# SoftCore_SA_P6.net
KiCad netlist of a schematic drawn in Altium Designer
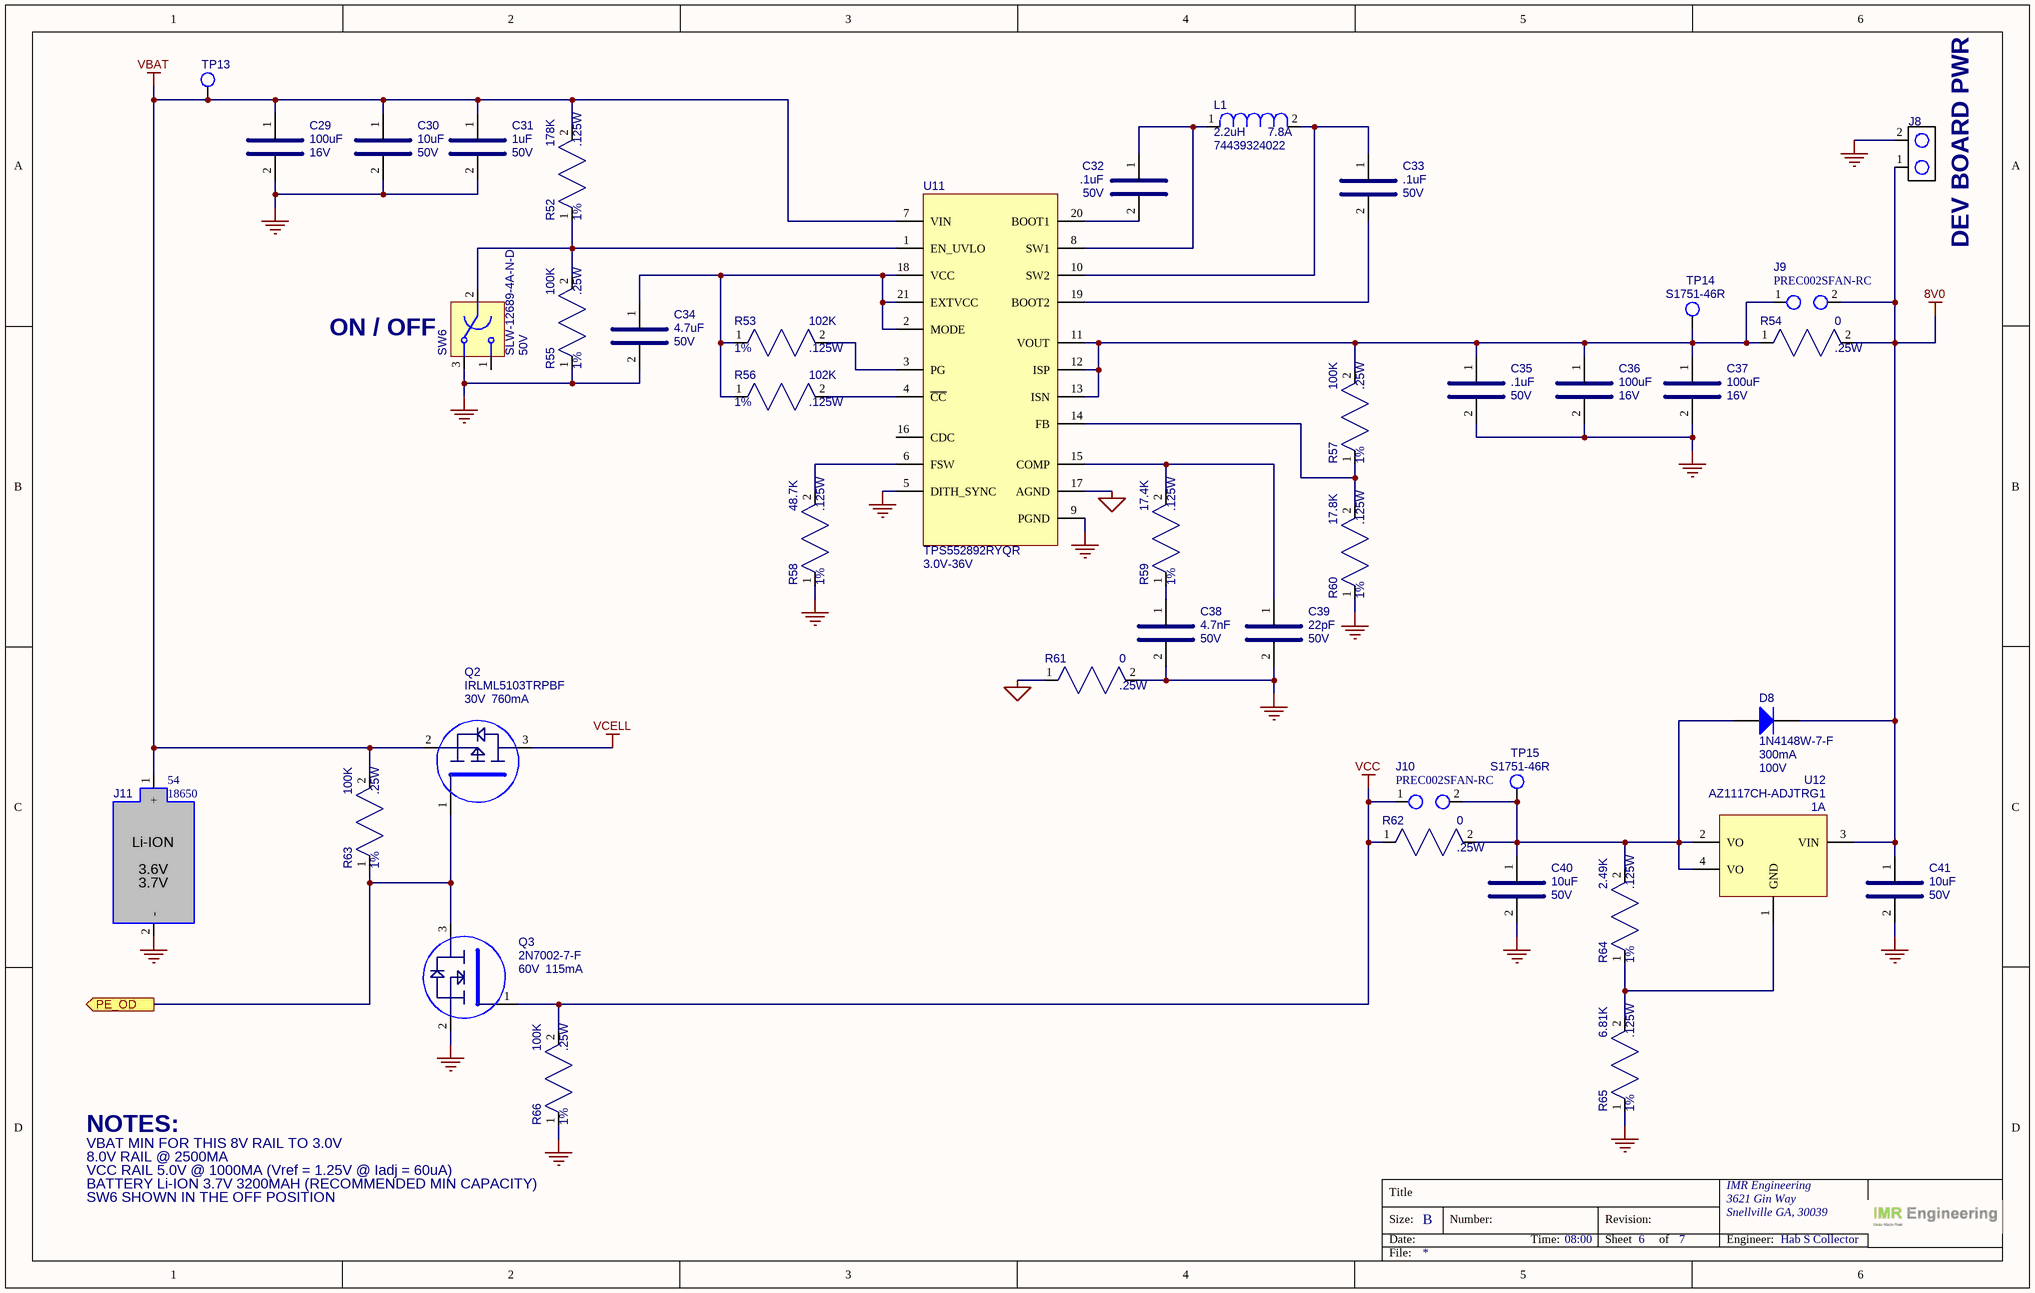
[diagram p0: SoftCore_SA_P6.SchDoc]

(export (version "E")
  (design (tool "Eeschema 10.0.6"))
  (components
    (comp (ref "C29")
      (value "100uF")
      (footprint "CAP_1210")
      (description "CAP CER 100UF 16V X7S SMD")
      (fields
        (field (name "MFG") "Taiyo Yuden")
        (field (name "VOLTAGE") "16V")
        (field (name "Comment") "EMK325ABJ107MM-P")
      )
      (libsource (lib "IMR_LIB_SCH_R2") (part "CAP_SMD_100UF_16V_SMD"))
    )
    (comp (ref "C30")
      (value "10uF")
      (footprint "CAP_0805")
      (description "CAP CER 10UF 50V X5R 0805")
      (fields
        (field (name "MFG") "Murata Electronics")
        (field (name "VOLTAGE") "50V")
        (field (name "Comment") "GRM21BR61H106KE43L")
      )
      (libsource (lib "IMR_LIB_SCH_R2") (part "CAP_SMD_10UF_50V_0805"))
    )
    (comp (ref "C31")
      (value "1uF")
      (footprint "CAP_0805")
      (description "CAP CER 1UF 50V X7R 0805")
      (fields
        (field (name "MFG") "KYOCERA AVX")
        (field (name "VOLTAGE") "50V")
        (field (name "Comment") "08055C105K4T2A")
      )
      (libsource (lib "IMR_LIB_SCH_R2") (part "CAP_SMD_1UF_50V_0805"))
    )
    (comp (ref "C32")
      (value ".1uF")
      (footprint "CAP_0805")
      (description "CAP CER 0.1UF 50V X7R 0805")
      (fields
        (field (name "MFG") "KYOCERA AVX")
        (field (name "VOLTAGE") "50V")
        (field (name "Comment") "KGM21NR71H104KT")
      )
      (libsource (lib "IMR_LIB_SCH_R2") (part "CAP_SMD_0.1UF_50V_0805"))
    )
    (comp (ref "C33")
      (value ".1uF")
      (footprint "CAP_0805")
      (description "CAP CER 0.1UF 50V X7R 0805")
      (fields
        (field (name "MFG") "KYOCERA AVX")
        (field (name "VOLTAGE") "50V")
        (field (name "Comment") "KGM21NR71H104KT")
      )
      (libsource (lib "IMR_LIB_SCH_R2") (part "CAP_SMD_0.1UF_50V_0805"))
    )
    (comp (ref "C34")
      (value "4.7uF")
      (footprint "CAP_0805")
      (description "CAP CER 4.7UF 50V X5R 0805")
      (fields
        (field (name "MFG") "Murata Electronics")
        (field (name "VOLTAGE") "50V")
        (field (name "Comment") "GRM21BR61H475KE51L")
      )
      (libsource (lib "IMR_LIB_SCH_R2") (part "CAP_SMD_4.7UF_50V_0805"))
    )
    (comp (ref "C35")
      (value ".1uF")
      (footprint "CAP_0805")
      (description "CAP CER 0.1UF 50V X7R 0805")
      (fields
        (field (name "MFG") "KYOCERA AVX")
        (field (name "VOLTAGE") "50V")
        (field (name "Comment") "KGM21NR71H104KT")
      )
      (libsource (lib "IMR_LIB_SCH_R2") (part "CAP_SMD_0.1UF_50V_0805"))
    )
    (comp (ref "C36")
      (value "100uF")
      (footprint "CAP_1210")
      (description "CAP CER 100UF 16V X7S SMD")
      (fields
        (field (name "MFG") "Taiyo Yuden")
        (field (name "VOLTAGE") "16V")
        (field (name "Comment") "EMK325ABJ107MM-P")
      )
      (libsource (lib "IMR_LIB_SCH_R2") (part "CAP_SMD_100UF_16V_SMD"))
    )
    (comp (ref "C37")
      (value "100uF")
      (footprint "CAP_1210")
      (description "CAP CER 100UF 16V X7S SMD")
      (fields
        (field (name "MFG") "Taiyo Yuden")
        (field (name "VOLTAGE") "16V")
        (field (name "Comment") "EMK325ABJ107MM-P")
      )
      (libsource (lib "IMR_LIB_SCH_R2") (part "CAP_SMD_100UF_16V_SMD"))
    )
    (comp (ref "C38")
      (value "4.7nF")
      (footprint "CAP_0805")
      (description "CAP CER 4.7NF 50V X7R 0805")
      (fields
        (field (name "MFG") "KEMET")
        (field (name "VOLTAGE") "50V")
        (field (name "Comment") "C0805C472K5RACAUTO")
      )
      (libsource (lib "IMR_LIB_SCH_R2") (part "CAP_SMD_4.7NF_50V_0805"))
    )
    (comp (ref "C39")
      (value "22pF")
      (footprint "CAP_0805")
      (description "CAP CER 22PF 50V X7R 0805")
      (fields
        (field (name "MFG") "KEMET")
        (field (name "VOLTAGE") "50V")
        (field (name "Comment") "C0805C220K5RACAUTO")
      )
      (libsource (lib "IMR_LIB_SCH_R2") (part "CAP_SMD_22PF_50V_0805"))
    )
    (comp (ref "C40")
      (value "10uF")
      (footprint "CAP_0805")
      (description "CAP CER 10UF 50V X5R 0805")
      (fields
        (field (name "MFG") "Murata Electronics")
        (field (name "VOLTAGE") "50V")
        (field (name "Comment") "GRM21BR61H106KE43L")
      )
      (libsource (lib "IMR_LIB_SCH_R2") (part "CAP_SMD_10UF_50V_0805"))
    )
    (comp (ref "C41")
      (value "10uF")
      (footprint "CAP_0805")
      (description "CAP CER 10UF 50V X5R 0805")
      (fields
        (field (name "MFG") "Murata Electronics")
        (field (name "VOLTAGE") "50V")
        (field (name "Comment") "GRM21BR61H106KE43L")
      )
      (libsource (lib "IMR_LIB_SCH_R2") (part "CAP_SMD_10UF_50V_0805"))
    )
    (comp (ref "D8")
      (value "100V")
      (footprint "SOD123")
      (description "RELAY REED SPDT 250MA 5V")
      (fields
        (field (name "MFG") "Diodes Inc")
        (field (name "MFG_PN") "1N4148W-7-F")
        (field (name "CURRENT") "300mA")
        (field (name "Comment") "1N4148W-7-F")
      )
      (libsource (lib "IMR_LIB_SCH_R2") (part "DIODE_1N4148W-7-F"))
    )
    (comp (ref "J8")
      (value "PREC002SFAN-RC")
      (footprint "HDR_1X2_100MILL")
      (description "CONN HEADER VERT 2POS 2.54MM")
      (fields (field (name "MFG") "Sullins Connector Solutions"))
      (libsource (lib "IMR_LIB_SCH_R2") (part "CONN_HEADER_2P_100MIL_VERT"))
    )
    (comp (ref "J9")
      (value "PREC002SFAN-RC")
      (footprint "HDR_1X2_100MILL")
      (description "CONN HEADER VERT 2POS 2.54MM")
      (fields (field (name "MFG") "Sullins Connector Solutions"))
      (libsource (lib "IMR_LIB_SCH_R2") (part "CONN_JUMPER_2P_100MIL_VERT"))
    )
    (comp (ref "J10")
      (value "PREC002SFAN-RC")
      (footprint "HDR_1X2_100MILL")
      (description "CONN HEADER VERT 2POS 2.54MM")
      (fields (field (name "MFG") "Sullins Connector Solutions"))
      (libsource (lib "IMR_LIB_SCH_R2") (part "CONN_JUMPER_2P_100MIL_VERT"))
    )
    (comp (ref "J11")
      (value "18650")
      (footprint "CONN_BATTERY_18650")
      (description "CONN HEADER VERT 2POS 2.54MM")
      (fields
        (field (name "MFG") "Keystone Electronics")
        (field (name "MFG_PN") "54")
        (field (name "Comment") "54")
      )
      (libsource (lib "IMR_LIB_SCH_R2") (part "CONN_BATT_18650"))
    )
    (comp (ref "L1")
      (value "2.2uH")
      (footprint "WE-XHMI_4030")
      (description "POWER INDUCTOR 4030; 2.2UH; 7.80")
      (fields
        (field (name "MFG") "Würth Elektronik")
        (field (name "TOLERANCE") "20%")
        (field (name "MFG_PN") "74439324022")
        (field (name "CURRENT") "7.8A")
      )
      (libsource (lib "IMR_LIB_SCH_R2") (part "INDUCTOR_74439324022"))
    )
    (comp (ref "Q2")
      (value "30V")
      (footprint "SOT-23")
      (description "MOSFET P-CH 30V 760MA SOT23")
      (fields
        (field (name "MFG") "Infineon Technologies")
        (field (name "MFG_PN") "IRLML5103TRPBF")
        (field (name "CURRENT") "760mA")
        (field (name "Comment") "IRLML5103TRPBF")
      )
      (libsource (lib "IMR_LIB_SCH_R2") (part "MOSFET_PCH_IRLML5103TRPBF"))
    )
    (comp (ref "Q3")
      (value "60V")
      (footprint "SOT-23")
      (description "MOSFET N-CH 60V 115MA SOT23-3")
      (fields
        (field (name "MFG") "Diodes Inc")
        (field (name "MFG_PN") "2N7002-7-F")
        (field (name "CURRENT") "115mA")
        (field (name "Comment") "2N7002-7-F")
      )
      (libsource (lib "IMR_LIB_SCH_R2") (part "MOSFET_NCH_2N7002-7-F"))
    )
    (comp (ref "R52")
      (value "178K")
      (footprint "RES_0805")
      (description "RES SMD 178K OHM 1% 1/8W 0805")
      (fields
        (field (name "MFG") "Yageo")
        (field (name "POWER") ".125W")
        (field (name "TOLERANCE") "1%")
        (field (name "Comment") "RC0805FR-07178KL")
      )
      (libsource (lib "IMR_LIB_SCH_R2") (part "RES_SMD_178K_0805_1/8W_1%"))
    )
    (comp (ref "R53")
      (value "102K")
      (footprint "RES_0805")
      (description "RES SMD 102K OHM 1% 1/8W 0805")
      (fields
        (field (name "MFG") "Yageo")
        (field (name "POWER") ".125W")
        (field (name "TOLERANCE") "1%")
        (field (name "Comment") "RC0805FR-07102KL")
      )
      (libsource (lib "IMR_LIB_SCH_R2") (part "RES_SMD_102K_0805_1/8W_1%"))
    )
    (comp (ref "R54")
      (value "0")
      (footprint "RES_0805")
      (description "RES SMD 0 OHM 1% 1/8W 0805")
      (fields (field (name "MFG") "Yageo") (field (name "TOLERANCE") "1%") (field (name "POWER") ".25W"))
      (libsource (lib "IMR_LIB_SCH_R2") (part "RES_SMD_0_0805_1/8W_1%"))
    )
    (comp (ref "R55")
      (value "100K")
      (footprint "RES_0805")
      (description "RES SMD 100K OHM 1% 1/4W 0805")
      (fields
        (field (name "MFG") "Yageo")
        (field (name "POWER") ".25W")
        (field (name "TOLERANCE") "1%")
        (field (name "Comment") "RC0805FR-07100KL")
      )
      (libsource (lib "IMR_LIB_SCH_R2") (part "RES_SMD_100K_0805_1/4W_1%"))
    )
    (comp (ref "R56")
      (value "102K")
      (footprint "RES_0805")
      (description "RES SMD 102K OHM 1% 1/8W 0805")
      (fields
        (field (name "MFG") "Yageo")
        (field (name "POWER") ".125W")
        (field (name "TOLERANCE") "1%")
        (field (name "Comment") "RC0805FR-07102KL")
      )
      (libsource (lib "IMR_LIB_SCH_R2") (part "RES_SMD_102K_0805_1/8W_1%"))
    )
    (comp (ref "R57")
      (value "100K")
      (footprint "RES_0805")
      (description "RES SMD 100K OHM 1% 1/4W 0805")
      (fields
        (field (name "MFG") "Yageo")
        (field (name "POWER") ".25W")
        (field (name "TOLERANCE") "1%")
        (field (name "Comment") "RC0805FR-07100KL")
      )
      (libsource (lib "IMR_LIB_SCH_R2") (part "RES_SMD_100K_0805_1/4W_1%"))
    )
    (comp (ref "R58")
      (value "48.7K")
      (footprint "RES_0805")
      (description "RES SMD 48.7K OHM 1% 1/8W 0805")
      (fields
        (field (name "MFG") "Yageo")
        (field (name "POWER") ".125W")
        (field (name "TOLERANCE") "1%")
        (field (name "Comment") "RC0805FR-0748K7L")
      )
      (libsource (lib "IMR_LIB_SCH_R2") (part "RES_SMD_48.7K_0805_1/8W_1%"))
    )
    (comp (ref "R59")
      (value "17.4K")
      (footprint "RES_0805")
      (description "RES SMD 17.4K OHM 1% 1/8W 0805")
      (fields
        (field (name "MFG") "Yageo")
        (field (name "POWER") ".125W")
        (field (name "TOLERANCE") "1%")
        (field (name "Comment") "RC0805FR-0717K4L")
      )
      (libsource (lib "IMR_LIB_SCH_R2") (part "RES_SMD_17.4K_0805_1/8W_1%"))
    )
    (comp (ref "R60")
      (value "17.8K")
      (footprint "RES_0805")
      (description "RES SMD 17.8K OHM 1% 1/8W 0805")
      (fields
        (field (name "MFG") "Yageo")
        (field (name "POWER") ".125W")
        (field (name "TOLERANCE") "1%")
        (field (name "Comment") "RC0805FR-0717K8L")
      )
      (libsource (lib "IMR_LIB_SCH_R2") (part "RES_SMD_17.8K_0805_1/8W_1%"))
    )
    (comp (ref "R61")
      (value "0")
      (footprint "RES_0805")
      (description "RES SMD 0 OHM 1% 1/8W 0805")
      (fields (field (name "MFG") "Yageo") (field (name "TOLERANCE") "1%") (field (name "POWER") ".25W"))
      (libsource (lib "IMR_LIB_SCH_R2") (part "RES_SMD_0_0805_1/8W_1%"))
    )
    (comp (ref "R62")
      (value "0")
      (footprint "RES_0805")
      (description "RES SMD 0 OHM 1% 1/8W 0805")
      (fields (field (name "MFG") "Yageo") (field (name "TOLERANCE") "1%") (field (name "POWER") ".25W"))
      (libsource (lib "IMR_LIB_SCH_R2") (part "RES_SMD_0_0805_1/8W_1%"))
    )
    (comp (ref "R63")
      (value "100K")
      (footprint "RES_0805")
      (description "RES SMD 100K OHM 1% 1/4W 0805")
      (fields
        (field (name "MFG") "Yageo")
        (field (name "POWER") ".25W")
        (field (name "TOLERANCE") "1%")
        (field (name "Comment") "RC0805FR-07100KL")
      )
      (libsource (lib "IMR_LIB_SCH_R2") (part "RES_SMD_100K_0805_1/4W_1%"))
    )
    (comp (ref "R64")
      (value "2.49K")
      (footprint "RES_0805")
      (description "RES SMD 2.49K OHM 1% 1/8W 0805")
      (fields
        (field (name "MFG") "Yageo")
        (field (name "POWER") ".125W")
        (field (name "TOLERANCE") "1%")
        (field (name "Comment") "RC0805FR-132K49L")
      )
      (libsource (lib "IMR_LIB_SCH_R2") (part "RES_SMD_2.49K_0805_1/8W_1%"))
    )
    (comp (ref "R65")
      (value "6.81K")
      (footprint "RES_0805")
      (description "RES SMD 6.81K OHM 1% 1/8W 0805")
      (fields
        (field (name "MFG") "Yageo")
        (field (name "POWER") ".125W")
        (field (name "TOLERANCE") "1%")
        (field (name "Comment") "RC0805FR-076K81L")
      )
      (libsource (lib "IMR_LIB_SCH_R2") (part "RES_SMD_6.81K_0805_1/8W_1%"))
    )
    (comp (ref "R66")
      (value "100K")
      (footprint "RES_0805")
      (description "RES SMD 100K OHM 1% 1/4W 0805")
      (fields
        (field (name "MFG") "Yageo")
        (field (name "POWER") ".25W")
        (field (name "TOLERANCE") "1%")
        (field (name "Comment") "RC0805FR-07100KL")
      )
      (libsource (lib "IMR_LIB_SCH_R2") (part "RES_SMD_100K_0805_1/4W_1%"))
    )
    (comp (ref "SW6")
      (value "50V")
      (footprint "SLW126894AND")
      (description "SWITCH SLIDE SPDT 300MA 50V")
      (fields
        (field (name "MFG") "Same Sky")
        (field (name "MFG_PN") "SLW-12689-4A-N-D")
        (field (name "Comment") "SLW-12689-4A-N-D")
      )
      (libsource (lib "IMR_LIB_SCH_R2") (part "SWITCH_SLW-12689-4A-N-D"))
    )
    (comp (ref "TP13")
      (value "~")
      (footprint "TEST_POINT_20MIL_TH")
      (description "TEST POINT TH 20MIL HOLE")
      (libsource (lib "IMR_LIB_SCH_R2") (part "CONN_TEST_POINT_TH_PAD_20MIL"))
    )
    (comp (ref "TP14")
      (value "S1751-46R")
      (footprint "HARWIN_S1751")
      (description "PCB TEST POINT CONNECT")
      (fields (field (name "MFG") "Harwin Inc") (field (name "MFG_PN") "S1751-46R"))
      (libsource (lib "IMR_LIB_SCH_R2") (part "CONN_TEST_POINT_S1751-46R"))
    )
    (comp (ref "TP15")
      (value "S1751-46R")
      (footprint "HARWIN_S1751")
      (description "PCB TEST POINT CONNECT")
      (fields (field (name "MFG") "Harwin Inc") (field (name "MFG_PN") "S1751-46R"))
      (libsource (lib "IMR_LIB_SCH_R2") (part "CONN_TEST_POINT_S1751-46R"))
    )
    (comp (ref "U11")
      (value "3.0V-36V")
      (footprint "CONV_TPS552892RYQR")
      (description "IC REG BUCK ADJ 1A 16HTSSOP")
      (fields
        (field (name "MFG") "Texas Instruments")
        (field (name "MFG_PN") "TPS552892RYQR")
        (field (name "Comment") "TPS552892RYQR")
      )
      (libsource (lib "IMR_LIB_SCH_R2") (part "IC_SMPS_TPS552892RYQR"))
    )
    (comp (ref "U12")
      (value "AZ1117CH-ADJTRG1")
      (footprint "SOT223")
      (description "IC REG BUCK ADJ 2A SOT23")
      (fields
        (field (name "MFG") "Diodes Incorporated")
        (field (name "CURRENT") "1A")
        (field (name "MFG_PN") "AZ1117CH-ADJTRG1")
      )
      (libsource (lib "IMR_LIB_SCH_R2") (part "IC_REG_AZ1117CH-ADJTRG1"))
    )
  )
  (nets
    (net (code "1") (name "/PE_OD") (class "Default")
      (node (ref "Q2") (pin "1") (pinfunction "G_1") (pintype "passive"))
      (node (ref "Q3") (pin "3") (pinfunction "C_3") (pintype "passive"))
      (node (ref "R63") (pin "1") (pinfunction "1_1") (pintype "passive"))
    )
    (net (code "2") (name "8V0") (class "Default")
      (node (ref "C41") (pin "1") (pinfunction "1_1") (pintype "passive"))
      (node (ref "D8") (pin "2") (pinfunction "K_2") (pintype "passive"))
      (node (ref "J8") (pin "1") (pintype "passive"))
      (node (ref "J9") (pin "2") (pintype "passive"))
      (node (ref "R54") (pin "2") (pinfunction "2_2") (pintype "passive"))
      (node (ref "U12") (pin "3") (pinfunction "VIN_3") (pintype "passive"))
    )
    (net (code "3") (name "AGND") (class "Default")
      (node (ref "R61") (pin "1") (pinfunction "1_1") (pintype "passive"))
      (node (ref "U11") (pin "17") (pinfunction "AGND_17") (pintype "passive"))
    )
    (net (code "4") (name "GND") (class "Default")
      (node (ref "C29") (pin "2") (pinfunction "2_2") (pintype "passive"))
      (node (ref "C30") (pin "2") (pinfunction "2_2") (pintype "passive"))
      (node (ref "C31") (pin "2") (pinfunction "2_2") (pintype "passive"))
      (node (ref "C34") (pin "2") (pinfunction "2_2") (pintype "passive"))
      (node (ref "C35") (pin "2") (pinfunction "2_2") (pintype "passive"))
      (node (ref "C36") (pin "2") (pinfunction "2_2") (pintype "passive"))
      (node (ref "C37") (pin "2") (pinfunction "2_2") (pintype "passive"))
      (node (ref "C38") (pin "2") (pinfunction "2_2") (pintype "passive"))
      (node (ref "C39") (pin "2") (pinfunction "2_2") (pintype "passive"))
      (node (ref "C40") (pin "2") (pinfunction "2_2") (pintype "passive"))
      (node (ref "C41") (pin "2") (pinfunction "2_2") (pintype "passive"))
      (node (ref "J11") (pin "2") (pinfunction "-_2") (pintype "passive"))
      (node (ref "J8") (pin "2") (pintype "passive"))
      (node (ref "Q3") (pin "2") (pinfunction "E_2") (pintype "passive"))
      (node (ref "R55") (pin "1") (pinfunction "1_1") (pintype "passive"))
      (node (ref "R58") (pin "1") (pinfunction "1_1") (pintype "passive"))
      (node (ref "R60") (pin "1") (pinfunction "1_1") (pintype "passive"))
      (node (ref "R61") (pin "2") (pinfunction "2_2") (pintype "passive"))
      (node (ref "R65") (pin "1") (pinfunction "1_1") (pintype "passive"))
      (node (ref "R66") (pin "1") (pinfunction "1_1") (pintype "passive"))
      (node (ref "SW6") (pin "3") (pintype "passive"))
      (node (ref "U11") (pin "5") (pinfunction "DITH_SYNC_5") (pintype "passive"))
      (node (ref "U11") (pin "9") (pinfunction "PGND_9") (pintype "passive"))
    )
    (net (code "5") (name "Net-(C38-Pad1)") (class "Default")
      (node (ref "C38") (pin "1") (pinfunction "1_1") (pintype "passive"))
      (node (ref "R59") (pin "1") (pinfunction "1_1") (pintype "passive"))
    )
    (net (code "6") (name "Net-(D8-A)") (class "Default")
      (node (ref "C40") (pin "1") (pinfunction "1_1") (pintype "passive"))
      (node (ref "D8") (pin "1") (pinfunction "A_1") (pintype "passive"))
      (node (ref "J10") (pin "2") (pintype "passive"))
      (node (ref "R62") (pin "2") (pinfunction "2_2") (pintype "passive"))
      (node (ref "R64") (pin "2") (pinfunction "2_2") (pintype "passive"))
      (node (ref "TP15") (pin "1") (pintype "passive"))
      (node (ref "U12") (pin "2") (pinfunction "VO_2") (pintype "passive"))
      (node (ref "U12") (pin "4") (pinfunction "VO_4") (pintype "passive"))
    )
    (net (code "7") (name "Net-(U11-BOOT1)") (class "Default")
      (node (ref "C32") (pin "2") (pinfunction "2_2") (pintype "passive"))
      (node (ref "U11") (pin "20") (pinfunction "BOOT1_20") (pintype "passive"))
    )
    (net (code "8") (name "Net-(U11-BOOT2)") (class "Default")
      (node (ref "C33") (pin "2") (pinfunction "2_2") (pintype "passive"))
      (node (ref "U11") (pin "19") (pinfunction "BOOT2_19") (pintype "passive"))
    )
    (net (code "9") (name "Net-(U11-COMP)") (class "Default")
      (node (ref "C39") (pin "1") (pinfunction "1_1") (pintype "passive"))
      (node (ref "R59") (pin "2") (pinfunction "2_2") (pintype "passive"))
      (node (ref "U11") (pin "15") (pinfunction "COMP_15") (pintype "passive"))
    )
    (net (code "10") (name "Net-(U11-EN_UVLO)") (class "Default")
      (node (ref "R52") (pin "1") (pinfunction "1_1") (pintype "passive"))
      (node (ref "R55") (pin "2") (pinfunction "2_2") (pintype "passive"))
      (node (ref "SW6") (pin "2") (pintype "passive"))
      (node (ref "U11") (pin "1") (pinfunction "EN_UVLO_1") (pintype "passive"))
    )
    (net (code "11") (name "Net-(U11-EXTVCC)") (class "Default")
      (node (ref "C34") (pin "1") (pinfunction "1_1") (pintype "passive"))
      (node (ref "R53") (pin "1") (pinfunction "1_1") (pintype "passive"))
      (node (ref "R56") (pin "1") (pinfunction "1_1") (pintype "passive"))
      (node (ref "U11") (pin "18") (pinfunction "VCC_18") (pintype "passive"))
      (node (ref "U11") (pin "2") (pinfunction "MODE_2") (pintype "passive"))
      (node (ref "U11") (pin "21") (pinfunction "EXTVCC_21") (pintype "passive"))
    )
    (net (code "12") (name "Net-(U11-FB)") (class "Default")
      (node (ref "R57") (pin "1") (pinfunction "1_1") (pintype "passive"))
      (node (ref "R60") (pin "2") (pinfunction "2_2") (pintype "passive"))
      (node (ref "U11") (pin "14") (pinfunction "FB_14") (pintype "passive"))
    )
    (net (code "13") (name "Net-(U11-FSW)") (class "Default")
      (node (ref "R58") (pin "2") (pinfunction "2_2") (pintype "passive"))
      (node (ref "U11") (pin "6") (pinfunction "FSW_6") (pintype "passive"))
    )
    (net (code "14") (name "Net-(U11-ISN)") (class "Default")
      (node (ref "C35") (pin "1") (pinfunction "1_1") (pintype "passive"))
      (node (ref "C36") (pin "1") (pinfunction "1_1") (pintype "passive"))
      (node (ref "C37") (pin "1") (pinfunction "1_1") (pintype "passive"))
      (node (ref "J9") (pin "1") (pintype "passive"))
      (node (ref "R54") (pin "1") (pinfunction "1_1") (pintype "passive"))
      (node (ref "R57") (pin "2") (pinfunction "2_2") (pintype "passive"))
      (node (ref "TP14") (pin "1") (pintype "passive"))
      (node (ref "U11") (pin "11") (pinfunction "VOUT_11") (pintype "passive"))
      (node (ref "U11") (pin "12") (pinfunction "ISP_12") (pintype "passive"))
      (node (ref "U11") (pin "13") (pinfunction "ISN_13") (pintype "passive"))
    )
    (net (code "15") (name "Net-(U11-PG)") (class "Default")
      (node (ref "R53") (pin "2") (pinfunction "2_2") (pintype "passive"))
      (node (ref "U11") (pin "3") (pinfunction "PG_3") (pintype "passive"))
    )
    (net (code "16") (name "Net-(U11-SW1)") (class "Default")
      (node (ref "C32") (pin "1") (pinfunction "1_1") (pintype "passive"))
      (node (ref "L1") (pin "1") (pinfunction "1_1") (pintype "passive"))
      (node (ref "U11") (pin "8") (pinfunction "SW1_8") (pintype "passive"))
    )
    (net (code "17") (name "Net-(U11-SW2)") (class "Default")
      (node (ref "C33") (pin "1") (pinfunction "1_1") (pintype "passive"))
      (node (ref "L1") (pin "2") (pinfunction "2_2") (pintype "passive"))
      (node (ref "U11") (pin "10") (pinfunction "SW2_10") (pintype "passive"))
    )
    (net (code "18") (name "Net-(U11-~{CC})") (class "Default")
      (node (ref "R56") (pin "2") (pinfunction "2_2") (pintype "passive"))
      (node (ref "U11") (pin "4") (pinfunction "~{CC}_4") (pintype "passive"))
    )
    (net (code "19") (name "Net-(U12-GND)") (class "Default")
      (node (ref "R64") (pin "1") (pinfunction "1_1") (pintype "passive"))
      (node (ref "R65") (pin "2") (pinfunction "2_2") (pintype "passive"))
      (node (ref "U12") (pin "1") (pinfunction "GND_1") (pintype "passive"))
    )
    (net (code "20") (name "VBAT") (class "Default")
      (node (ref "C29") (pin "1") (pinfunction "1_1") (pintype "passive"))
      (node (ref "C30") (pin "1") (pinfunction "1_1") (pintype "passive"))
      (node (ref "C31") (pin "1") (pinfunction "1_1") (pintype "passive"))
      (node (ref "J11") (pin "1") (pinfunction "+_1") (pintype "passive"))
      (node (ref "Q2") (pin "2") (pinfunction "S_2") (pintype "passive"))
      (node (ref "R52") (pin "2") (pinfunction "2_2") (pintype "passive"))
      (node (ref "R63") (pin "2") (pinfunction "2_2") (pintype "passive"))
      (node (ref "TP13") (pin "1") (pintype "passive"))
      (node (ref "U11") (pin "7") (pinfunction "VIN_7") (pintype "passive"))
    )
    (net (code "21") (name "VCC") (class "Default")
      (node (ref "J10") (pin "1") (pintype "passive"))
      (node (ref "Q3") (pin "1") (pinfunction "B_1") (pintype "passive"))
      (node (ref "R62") (pin "1") (pinfunction "1_1") (pintype "passive"))
      (node (ref "R66") (pin "2") (pinfunction "2_2") (pintype "passive"))
    )
    (net (code "22") (name "VCELL") (class "Default")
      (node (ref "Q2") (pin "3") (pinfunction "D_3") (pintype "passive"))
    )
    (net (code "23") (name "unconnected-(SW6-Pad1)") (class "Default")
      (node (ref "SW6") (pin "1") (pintype "passive"))
    )
    (net (code "24") (name "unconnected-(U11-CDC-Pad16)") (class "Default")
      (node (ref "U11") (pin "16") (pinfunction "CDC_16") (pintype "passive"))
    )
  )
)
